# CPU.net
KiCad netlist of a schematic drawn in Altium Designer
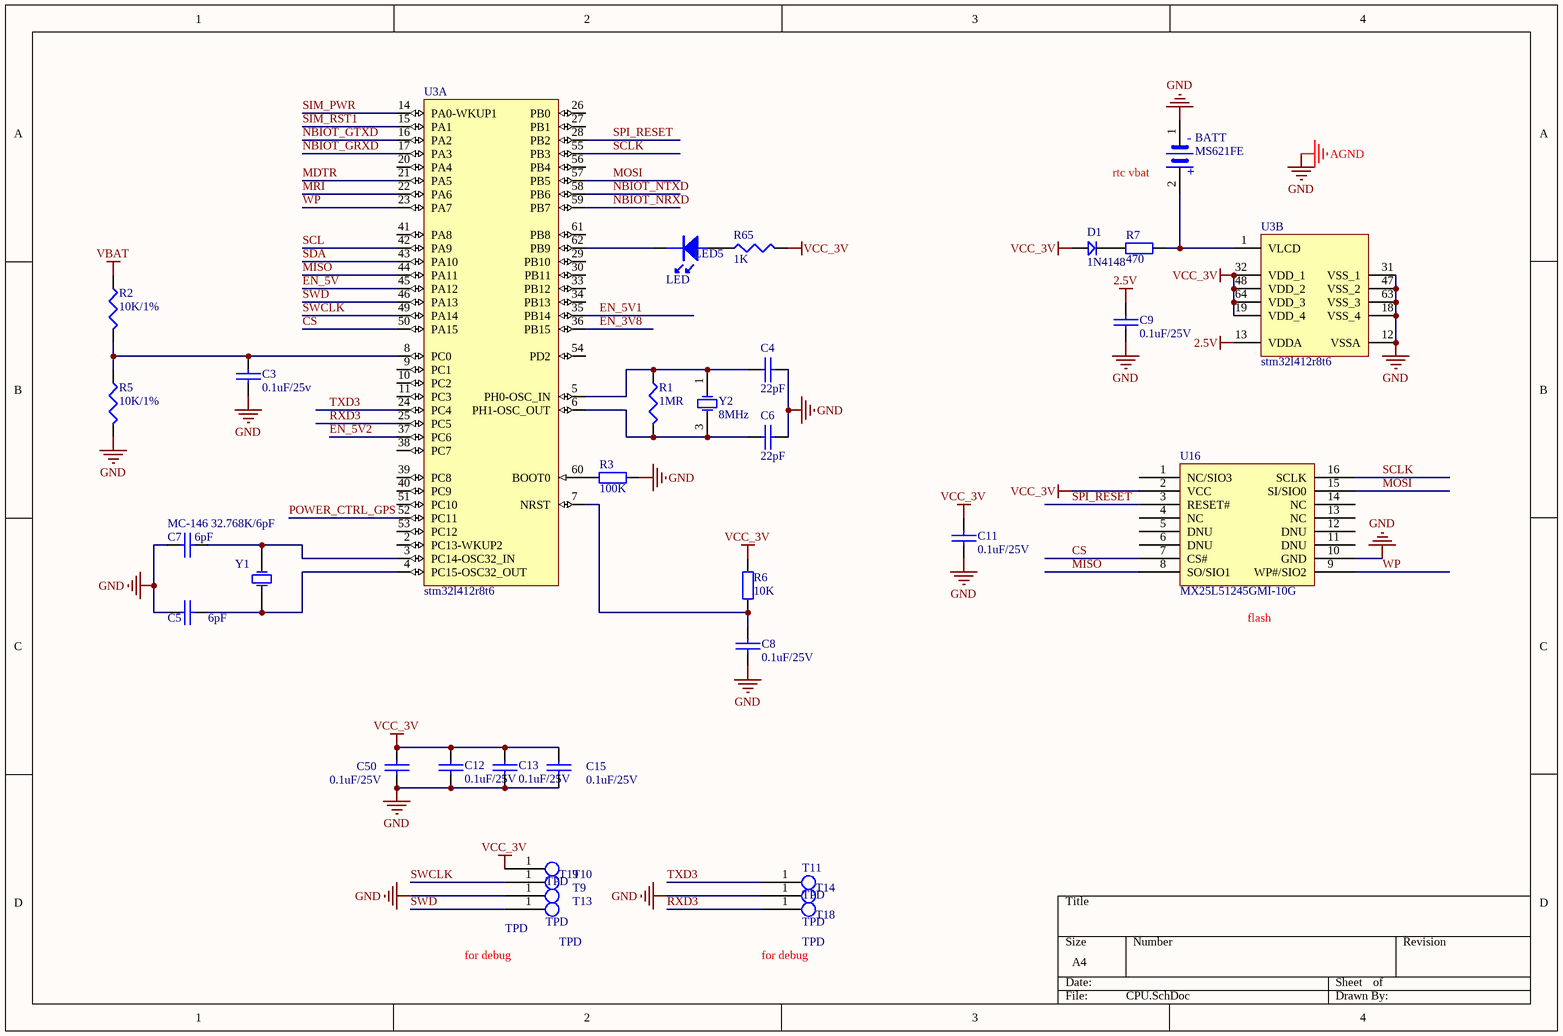
[diagram p0: CPU.SchDoc]

(export (version "E")
  (design (tool "Eeschema 10.0.6"))
  (components
    (comp (ref "BATT") (value "MS621FE") (footprint "MS621FE") (libsource (lib "Myself_1") (part "SBatery")))
    (comp (ref "C3")
      (value "0.1uF/25v")
      (footprint "0402c")
      (description "Capacitor")
      (libsource (lib "SM") (part "CAP"))
    )
    (comp (ref "C4")
      (value "22pF")
      (footprint "0402c")
      (description "Capacitor")
      (libsource (lib "SM") (part "CAP"))
    )
    (comp (ref "C5")
      (value "6pF")
      (footprint "0402c")
      (description "Capacitor")
      (libsource (lib "SM") (part "CAP"))
    )
    (comp (ref "C6")
      (value "22pF")
      (footprint "0402c")
      (description "Capacitor")
      (libsource (lib "SM") (part "CAP"))
    )
    (comp (ref "C7")
      (value "6pF")
      (footprint "0402c")
      (description "Capacitor")
      (libsource (lib "SM") (part "CAP"))
    )
    (comp (ref "C8")
      (value "0.1uF/25V")
      (footprint "0402C")
      (description "Capacitor")
      (libsource (lib "ZWLIntegrated_Library") (part "CAP"))
    )
    (comp (ref "C9")
      (value "0.1uF/25V")
      (footprint "0402C")
      (description "Capacitor")
      (libsource (lib "ZWLIntegrated_Library") (part "CAP"))
    )
    (comp (ref "C11")
      (value "0.1uF/25V")
      (footprint "0402C")
      (description "Capacitor")
      (libsource (lib "ZWLIntegrated_Library") (part "CAP"))
    )
    (comp (ref "C12")
      (value "0.1uF/25V")
      (footprint "0402C")
      (description "Capacitor")
      (libsource (lib "ZWLIntegrated_Library") (part "CAP"))
    )
    (comp (ref "C13")
      (value "0.1uF/25V")
      (footprint "0402C")
      (description "Capacitor")
      (libsource (lib "ZWLIntegrated_Library") (part "CAP"))
    )
    (comp (ref "C15")
      (value "0.1uF/25V")
      (footprint "0402C")
      (description "Capacitor")
      (libsource (lib "ZWLIntegrated_Library") (part "CAP"))
    )
    (comp (ref "C50")
      (value "0.1uF/25V")
      (footprint "0402C")
      (description "Capacitor")
      (libsource (lib "ZWLIntegrated_Library") (part "CAP"))
    )
    (comp (ref "D1")
      (value "1N4148")
      (footprint "DIODE_SOP")
      (libsource (lib "Explorer STM32F407封装库") (part "D"))
    )
    (comp (ref "LED5") (value "LED") (footprint "0603LED") (libsource (lib "我的元件库") (part "LED")))
    (comp (ref "R1")
      (value "1MR")
      (footprint "0402R")
      (description "Resistor")
      (fields (field (name "PUBLISHER") "Altium Limited"))
      (libsource (lib "SM") (part "Res3"))
    )
    (comp (ref "R2")
      (value "10K/1%")
      (footprint "0402R")
      (libsource (lib "ZWLIntegrated_Library") (part "RES1"))
    )
    (comp (ref "R3")
      (value "100K")
      (footprint "0402R")
      (description "Resistor")
      (fields (field (name "PUBLISHER") "Altium Limited"))
      (libsource (lib "Miscellaneous Devices") (part "Res2"))
    )
    (comp (ref "R5")
      (value "10K/1%")
      (footprint "0402R")
      (libsource (lib "ZWLIntegrated_Library") (part "RES1"))
    )
    (comp (ref "R6")
      (value "10K")
      (footprint "0402R")
      (description "Resistor")
      (fields (field (name "PUBLISHER") "Altium Limited"))
      (libsource (lib "") (part "Res2_1"))
    )
    (comp (ref "R7")
      (value "470")
      (footprint "0402R")
      (description "Resistor")
      (fields (field (name "PUBLISHER") "Altium Limited"))
      (libsource (lib "Miscellaneous Devices") (part "Res2"))
    )
    (comp (ref "R65")
      (value "1K")
      (footprint "0402R")
      (libsource (lib "ZWLIntegrated_Library") (part "RES1"))
    )
    (comp (ref "T9") (value "TPD") (footprint "Pcblib_20110825:TPd") (libsource (lib "stm32") (part "TPD")))
    (comp (ref "T10") (value "TPD") (footprint "Pcblib_20110825:TPd") (libsource (lib "stm32") (part "TPD")))
    (comp (ref "T11") (value "TPD") (footprint "Pcblib_20110825:TPd") (libsource (lib "stm32") (part "TPD")))
    (comp (ref "T13") (value "TPD") (footprint "Pcblib_20110825:TPd") (libsource (lib "stm32") (part "TPD")))
    (comp (ref "T14") (value "TPD") (footprint "Pcblib_20110825:TPd") (libsource (lib "stm32") (part "TPD")))
    (comp (ref "T18") (value "TPD") (footprint "Pcblib_20110825:TPd") (libsource (lib "stm32") (part "TPD")))
    (comp (ref "T19") (value "TPD") (footprint "Pcblib_20110825:TPd") (libsource (lib "stm32") (part "TPD")))
    (comp (ref "U3")
      (value "stm32l412r8t6")
      (footprint "LQFP-64")
      (fields (field (name "MANUFACTURER") "STMicroelectronics") (field (name "PARTNUMBER") "STM32L100R8T6"))
      (libsource (lib "STMicroelectronics STM32 L1") (part "STM32L100R8T6"))
    )
    (comp (ref "U16")
      (value "MX25L51245GMI-10G")
      (footprint "SOP127P1030X239-16N")
      (libsource (lib "stm32") (part "MX25L51245GMI-10G"))
    )
    (comp (ref "Y1")
      (value "MC-146 32.768K/6pF")
      (footprint "32.768K")
      (description "Crystal Oscillator")
      (fields (field (name "PUBLISHER") "Altium Limited"))
      (libsource (lib "Miscellaneous Devices") (part "XTAL"))
    )
    (comp (ref "Y2")
      (value "8MHz")
      (footprint "OSCILLATOR-3.2X2.5")
      (description "Crystal Oscillator")
      (fields (field (name "PUBLISHER") "Altium Limited"))
      (libsource (lib "") (part "XTAL_1"))
    )
  )
  (nets
    (net (code "1") (name "/CS") (class "Default")
      (node (ref "U16") (pin "7") (pinfunction "CS#_7") (pintype "passive"))
      (node (ref "U3") (pin "50") (pinfunction "PA15_50") (pintype "bidirectional"))
    )
    (net (code "2") (name "/EN_3V8") (class "Default")
      (node (ref "U3") (pin "36") (pinfunction "PB15_36") (pintype "bidirectional"))
    )
    (net (code "3") (name "/EN_5V") (class "Default")
      (node (ref "U3") (pin "45") (pinfunction "PA12_45") (pintype "bidirectional"))
    )
    (net (code "4") (name "/EN_5V1") (class "Default")
      (node (ref "U3") (pin "35") (pinfunction "PB14_35") (pintype "bidirectional"))
    )
    (net (code "5") (name "/EN_5V2") (class "Default")
      (node (ref "U3") (pin "37") (pinfunction "PC6_37") (pintype "bidirectional"))
    )
    (net (code "6") (name "/MDTR") (class "Default")
      (node (ref "U3") (pin "21") (pinfunction "PA5_21") (pintype "bidirectional"))
    )
    (net (code "7") (name "/MISO") (class "Default")
      (node (ref "U16") (pin "8") (pinfunction "SO/SIO1_8") (pintype "passive"))
      (node (ref "U3") (pin "44") (pinfunction "PA11_44") (pintype "bidirectional"))
    )
    (net (code "8") (name "/MOSI") (class "Default")
      (node (ref "U16") (pin "15") (pinfunction "SI/SIO0_15") (pintype "passive"))
      (node (ref "U3") (pin "57") (pinfunction "PB5_57") (pintype "bidirectional"))
    )
    (net (code "9") (name "/MRI") (class "Default")
      (node (ref "U3") (pin "22") (pinfunction "PA6_22") (pintype "bidirectional"))
    )
    (net (code "10") (name "/NBIOT_GRXD") (class "Default")
      (node (ref "U3") (pin "17") (pinfunction "PA3_17") (pintype "bidirectional"))
    )
    (net (code "11") (name "/NBIOT_GTXD") (class "Default")
      (node (ref "U3") (pin "16") (pinfunction "PA2_16") (pintype "bidirectional"))
    )
    (net (code "12") (name "/NBIOT_NRXD") (class "Default")
      (node (ref "U3") (pin "59") (pinfunction "PB7_59") (pintype "bidirectional"))
    )
    (net (code "13") (name "/NBIOT_NTXD") (class "Default")
      (node (ref "U3") (pin "58") (pinfunction "PB6_58") (pintype "bidirectional"))
    )
    (net (code "14") (name "/POWER_CTRL_GPS") (class "Default")
      (node (ref "U3") (pin "52") (pinfunction "PC11_52") (pintype "bidirectional"))
    )
    (net (code "15") (name "/RXD3") (class "Default")
      (node (ref "T18") (pin "1") (pintype "passive"))
      (node (ref "U3") (pin "25") (pinfunction "PC5_25") (pintype "bidirectional"))
    )
    (net (code "16") (name "/SCL") (class "Default")
      (node (ref "U3") (pin "42") (pinfunction "PA9_42") (pintype "bidirectional"))
    )
    (net (code "17") (name "/SCLK") (class "Default")
      (node (ref "U16") (pin "16") (pinfunction "SCLK_16") (pintype "passive"))
      (node (ref "U3") (pin "55") (pinfunction "PB3_55") (pintype "bidirectional"))
    )
    (net (code "18") (name "/SDA") (class "Default")
      (node (ref "U3") (pin "43") (pinfunction "PA10_43") (pintype "bidirectional"))
    )
    (net (code "19") (name "/SIM_PWR") (class "Default")
      (node (ref "U3") (pin "14") (pinfunction "PA0-WKUP1_14") (pintype "bidirectional"))
    )
    (net (code "20") (name "/SIM_RST1") (class "Default")
      (node (ref "U3") (pin "15") (pinfunction "PA1_15") (pintype "bidirectional"))
    )
    (net (code "21") (name "/SPI_RESET") (class "Default")
      (node (ref "U16") (pin "3") (pinfunction "RESET#_3") (pintype "passive"))
      (node (ref "U3") (pin "28") (pinfunction "PB2_28") (pintype "bidirectional"))
    )
    (net (code "22") (name "/SWCLK") (class "Default")
      (node (ref "T10") (pin "1") (pintype "passive"))
      (node (ref "U3") (pin "49") (pinfunction "PA14_49") (pintype "bidirectional"))
    )
    (net (code "23") (name "/SWD") (class "Default")
      (node (ref "T9") (pin "1") (pintype "passive"))
      (node (ref "U3") (pin "46") (pinfunction "PA13_46") (pintype "bidirectional"))
    )
    (net (code "24") (name "/TXD3") (class "Default")
      (node (ref "T11") (pin "1") (pintype "passive"))
      (node (ref "U3") (pin "24") (pinfunction "PC4_24") (pintype "bidirectional"))
    )
    (net (code "25") (name "/WP") (class "Default")
      (node (ref "U16") (pin "9") (pinfunction "WP#/SIO2_9") (pintype "passive"))
      (node (ref "U3") (pin "23") (pinfunction "PA7_23") (pintype "bidirectional"))
    )
    (net (code "26") (name "2.5V") (class "Default")
      (node (ref "C9") (pin "2") (pinfunction "2_2") (pintype "passive"))
      (node (ref "U3") (pin "13") (pinfunction "VDDA_13") (pintype "power_in"))
    )
    (net (code "27") (name "AGND") (class "Default")
      (node (ref "BATT") (pin "1") (pinfunction "1_1") (pintype "passive"))
      (node (ref "C11") (pin "1") (pinfunction "1_1") (pintype "passive"))
      (node (ref "C12") (pin "1") (pinfunction "1_1") (pintype "passive"))
      (node (ref "C13") (pin "1") (pinfunction "1_1") (pintype "passive"))
      (node (ref "C15") (pin "1") (pinfunction "1_1") (pintype "passive"))
      (node (ref "C3") (pin "2") (pinfunction "2_2") (pintype "passive"))
      (node (ref "C4") (pin "1") (pinfunction "1_1") (pintype "passive"))
      (node (ref "C5") (pin "2") (pinfunction "2_2") (pintype "passive"))
      (node (ref "C50") (pin "1") (pinfunction "1_1") (pintype "passive"))
      (node (ref "C6") (pin "1") (pinfunction "1_1") (pintype "passive"))
      (node (ref "C7") (pin "2") (pinfunction "2_2") (pintype "passive"))
      (node (ref "C8") (pin "1") (pinfunction "1_1") (pintype "passive"))
      (node (ref "C9") (pin "1") (pinfunction "1_1") (pintype "passive"))
      (node (ref "R3") (pin "2") (pinfunction "2_2") (pintype "passive"))
      (node (ref "R5") (pin "2") (pinfunction "2_2") (pintype "passive"))
      (node (ref "T13") (pin "1") (pintype "passive"))
      (node (ref "T14") (pin "1") (pintype "passive"))
      (node (ref "U16") (pin "10") (pinfunction "GND_10") (pintype "passive"))
      (node (ref "U3") (pin "12") (pinfunction "VSSA_12") (pintype "power_in"))
      (node (ref "U3") (pin "18") (pinfunction "VSS_4_18") (pintype "power_in"))
      (node (ref "U3") (pin "31") (pinfunction "VSS_1_31") (pintype "power_in"))
      (node (ref "U3") (pin "47") (pinfunction "VSS_2_47") (pintype "power_in"))
      (node (ref "U3") (pin "63") (pinfunction "VSS_3_63") (pintype "power_in"))
    )
    (net (code "28") (name "Net-(D1-Pad2)") (class "Default")
      (node (ref "D1") (pin "2") (pintype "passive"))
      (node (ref "R7") (pin "1") (pinfunction "1_1") (pintype "passive"))
    )
    (net (code "29") (name "Net-(LED5-Pad1)") (class "Default")
      (node (ref "LED5") (pin "1") (pinfunction "1_1") (pintype "passive"))
      (node (ref "R65") (pin "1") (pinfunction "1_1") (pintype "passive"))
    )
    (net (code "30") (name "Net-(U3A-BOOT0)") (class "Default")
      (node (ref "R3") (pin "1") (pinfunction "1_1") (pintype "passive"))
      (node (ref "U3") (pin "60") (pinfunction "BOOT0_60") (pintype "input"))
    )
    (net (code "31") (name "Net-(U3A-NRST)") (class "Default")
      (node (ref "C8") (pin "2") (pinfunction "2_2") (pintype "passive"))
      (node (ref "R6") (pin "2") (pinfunction "2_2") (pintype "passive"))
      (node (ref "U3") (pin "7") (pinfunction "NRST_7") (pintype "bidirectional"))
    )
    (net (code "32") (name "Net-(U3A-PB9)") (class "Default")
      (node (ref "LED5") (pin "2") (pinfunction "2_2") (pintype "passive"))
      (node (ref "U3") (pin "62") (pinfunction "PB9_62") (pintype "bidirectional"))
    )
    (net (code "33") (name "Net-(U3A-PC0)") (class "Default")
      (node (ref "C3") (pin "1") (pinfunction "1_1") (pintype "passive"))
      (node (ref "R2") (pin "2") (pinfunction "2_2") (pintype "passive"))
      (node (ref "R5") (pin "1") (pinfunction "1_1") (pintype "passive"))
      (node (ref "U3") (pin "8") (pinfunction "PC0_8") (pintype "bidirectional"))
    )
    (net (code "34") (name "Net-(U3A-PC14-OSC32_IN)") (class "Default")
      (node (ref "C7") (pin "1") (pinfunction "1_1") (pintype "passive"))
      (node (ref "U3") (pin "3") (pinfunction "PC14-OSC32_IN_3") (pintype "bidirectional"))
      (node (ref "Y1") (pin "1") (pinfunction "OSC1_1") (pintype "passive"))
    )
    (net (code "35") (name "Net-(U3A-PC15-OSC32_OUT)") (class "Default")
      (node (ref "C5") (pin "1") (pinfunction "1_1") (pintype "passive"))
      (node (ref "U3") (pin "4") (pinfunction "PC15-OSC32_OUT_4") (pintype "bidirectional"))
      (node (ref "Y1") (pin "2") (pinfunction "OSC2_2") (pintype "passive"))
    )
    (net (code "36") (name "Net-(U3A-PH0-OSC_IN)") (class "Default")
      (node (ref "C4") (pin "2") (pinfunction "2_2") (pintype "passive"))
      (node (ref "R1") (pin "1") (pinfunction "1_1") (pintype "passive"))
      (node (ref "U3") (pin "5") (pinfunction "PH0-OSC_IN_5") (pintype "bidirectional"))
      (node (ref "Y2") (pin "1") (pinfunction "OSC1_1") (pintype "passive"))
    )
    (net (code "37") (name "Net-(U3A-PH1-OSC_OUT)") (class "Default")
      (node (ref "C6") (pin "2") (pinfunction "2_2") (pintype "passive"))
      (node (ref "R1") (pin "2") (pinfunction "2_2") (pintype "passive"))
      (node (ref "U3") (pin "6") (pinfunction "PH1-OSC_OUT_6") (pintype "bidirectional"))
      (node (ref "Y2") (pin "3") (pinfunction "OSC2_3") (pintype "passive"))
    )
    (net (code "38") (name "Net-(U3B-VLCD)") (class "Default")
      (node (ref "BATT") (pin "2") (pinfunction "2_2") (pintype "passive"))
      (node (ref "R7") (pin "2") (pinfunction "2_2") (pintype "passive"))
      (node (ref "U3") (pin "1") (pinfunction "VLCD_1") (pintype "power_in"))
    )
    (net (code "39") (name "VBAT") (class "Default")
      (node (ref "R2") (pin "1") (pinfunction "1_1") (pintype "passive"))
    )
    (net (code "40") (name "VCC_3V") (class "Default")
      (node (ref "C11") (pin "2") (pinfunction "2_2") (pintype "passive"))
      (node (ref "C12") (pin "2") (pinfunction "2_2") (pintype "passive"))
      (node (ref "C13") (pin "2") (pinfunction "2_2") (pintype "passive"))
      (node (ref "C15") (pin "2") (pinfunction "2_2") (pintype "passive"))
      (node (ref "C50") (pin "2") (pinfunction "2_2") (pintype "passive"))
      (node (ref "D1") (pin "1") (pintype "passive"))
      (node (ref "R6") (pin "1") (pinfunction "1_1") (pintype "passive"))
      (node (ref "R65") (pin "2") (pinfunction "2_2") (pintype "passive"))
      (node (ref "T19") (pin "1") (pintype "passive"))
      (node (ref "U16") (pin "2") (pinfunction "VCC_2") (pintype "passive"))
      (node (ref "U3") (pin "19") (pinfunction "VDD_4_19") (pintype "power_in"))
      (node (ref "U3") (pin "32") (pinfunction "VDD_1_32") (pintype "power_in"))
      (node (ref "U3") (pin "48") (pinfunction "VDD_2_48") (pintype "power_in"))
      (node (ref "U3") (pin "64") (pinfunction "VDD_3_64") (pintype "power_in"))
    )
    (net (code "41") (name "unconnected-(U3A-PA4-Pad20)") (class "Default")
      (node (ref "U3") (pin "20") (pinfunction "PA4_20") (pintype "bidirectional"))
    )
    (net (code "42") (name "unconnected-(U3A-PA8-Pad41)") (class "Default")
      (node (ref "U3") (pin "41") (pinfunction "PA8_41") (pintype "bidirectional"))
    )
    (net (code "43") (name "unconnected-(U3A-PB0-Pad26)") (class "Default")
      (node (ref "U3") (pin "26") (pinfunction "PB0_26") (pintype "bidirectional"))
    )
    (net (code "44") (name "unconnected-(U3A-PB1-Pad27)") (class "Default")
      (node (ref "U3") (pin "27") (pinfunction "PB1_27") (pintype "bidirectional"))
    )
    (net (code "45") (name "unconnected-(U3A-PB4-Pad56)") (class "Default")
      (node (ref "U3") (pin "56") (pinfunction "PB4_56") (pintype "bidirectional"))
    )
    (net (code "46") (name "unconnected-(U3A-PB8-Pad61)") (class "Default")
      (node (ref "U3") (pin "61") (pinfunction "PB8_61") (pintype "bidirectional"))
    )
    (net (code "47") (name "unconnected-(U3A-PB10-Pad29)") (class "Default")
      (node (ref "U3") (pin "29") (pinfunction "PB10_29") (pintype "bidirectional"))
    )
    (net (code "48") (name "unconnected-(U3A-PB11-Pad30)") (class "Default")
      (node (ref "U3") (pin "30") (pinfunction "PB11_30") (pintype "bidirectional"))
    )
    (net (code "49") (name "unconnected-(U3A-PB12-Pad33)") (class "Default")
      (node (ref "U3") (pin "33") (pinfunction "PB12_33") (pintype "bidirectional"))
    )
    (net (code "50") (name "unconnected-(U3A-PB13-Pad34)") (class "Default")
      (node (ref "U3") (pin "34") (pinfunction "PB13_34") (pintype "bidirectional"))
    )
    (net (code "51") (name "unconnected-(U3A-PC1-Pad9)") (class "Default")
      (node (ref "U3") (pin "9") (pinfunction "PC1_9") (pintype "bidirectional"))
    )
    (net (code "52") (name "unconnected-(U3A-PC2-Pad10)") (class "Default")
      (node (ref "U3") (pin "10") (pinfunction "PC2_10") (pintype "bidirectional"))
    )
    (net (code "53") (name "unconnected-(U3A-PC3-Pad11)") (class "Default")
      (node (ref "U3") (pin "11") (pinfunction "PC3_11") (pintype "bidirectional"))
    )
    (net (code "54") (name "unconnected-(U3A-PC7-Pad38)") (class "Default")
      (node (ref "U3") (pin "38") (pinfunction "PC7_38") (pintype "bidirectional"))
    )
    (net (code "55") (name "unconnected-(U3A-PC8-Pad39)") (class "Default")
      (node (ref "U3") (pin "39") (pinfunction "PC8_39") (pintype "bidirectional"))
    )
    (net (code "56") (name "unconnected-(U3A-PC9-Pad40)") (class "Default")
      (node (ref "U3") (pin "40") (pinfunction "PC9_40") (pintype "bidirectional"))
    )
    (net (code "57") (name "unconnected-(U3A-PC10-Pad51)") (class "Default")
      (node (ref "U3") (pin "51") (pinfunction "PC10_51") (pintype "bidirectional"))
    )
    (net (code "58") (name "unconnected-(U3A-PC12-Pad53)") (class "Default")
      (node (ref "U3") (pin "53") (pinfunction "PC12_53") (pintype "bidirectional"))
    )
    (net (code "59") (name "unconnected-(U3A-PC13-WKUP2-Pad2)") (class "Default")
      (node (ref "U3") (pin "2") (pinfunction "PC13-WKUP2_2") (pintype "bidirectional"))
    )
    (net (code "60") (name "unconnected-(U3A-PD2-Pad54)") (class "Default")
      (node (ref "U3") (pin "54") (pinfunction "PD2_54") (pintype "bidirectional"))
    )
    (net (code "61") (name "unconnected-(U16-DNU-Pad5)") (class "Default")
      (node (ref "U16") (pin "5") (pinfunction "DNU_5") (pintype "passive"))
    )
    (net (code "62") (name "unconnected-(U16-DNU-Pad6)") (class "Default")
      (node (ref "U16") (pin "6") (pinfunction "DNU_6") (pintype "passive"))
    )
    (net (code "63") (name "unconnected-(U16-DNU-Pad11)") (class "Default")
      (node (ref "U16") (pin "11") (pinfunction "DNU_11") (pintype "passive"))
    )
    (net (code "64") (name "unconnected-(U16-DNU-Pad12)") (class "Default")
      (node (ref "U16") (pin "12") (pinfunction "DNU_12") (pintype "passive"))
    )
    (net (code "65") (name "unconnected-(U16-NC-Pad4)") (class "Default")
      (node (ref "U16") (pin "4") (pinfunction "NC_4") (pintype "passive"))
    )
    (net (code "66") (name "unconnected-(U16-NC-Pad13)") (class "Default")
      (node (ref "U16") (pin "13") (pinfunction "NC_13") (pintype "passive"))
    )
    (net (code "67") (name "unconnected-(U16-NC-Pad14)") (class "Default")
      (node (ref "U16") (pin "14") (pinfunction "NC_14") (pintype "passive"))
    )
    (net (code "68") (name "unconnected-(U16-NC{slash}SIO3-Pad1)") (class "Default")
      (node (ref "U16") (pin "1") (pinfunction "NC/SIO3_1") (pintype "passive"))
    )
  )
)
